# Power.net
KiCad netlist of a schematic drawn in Altium Designer
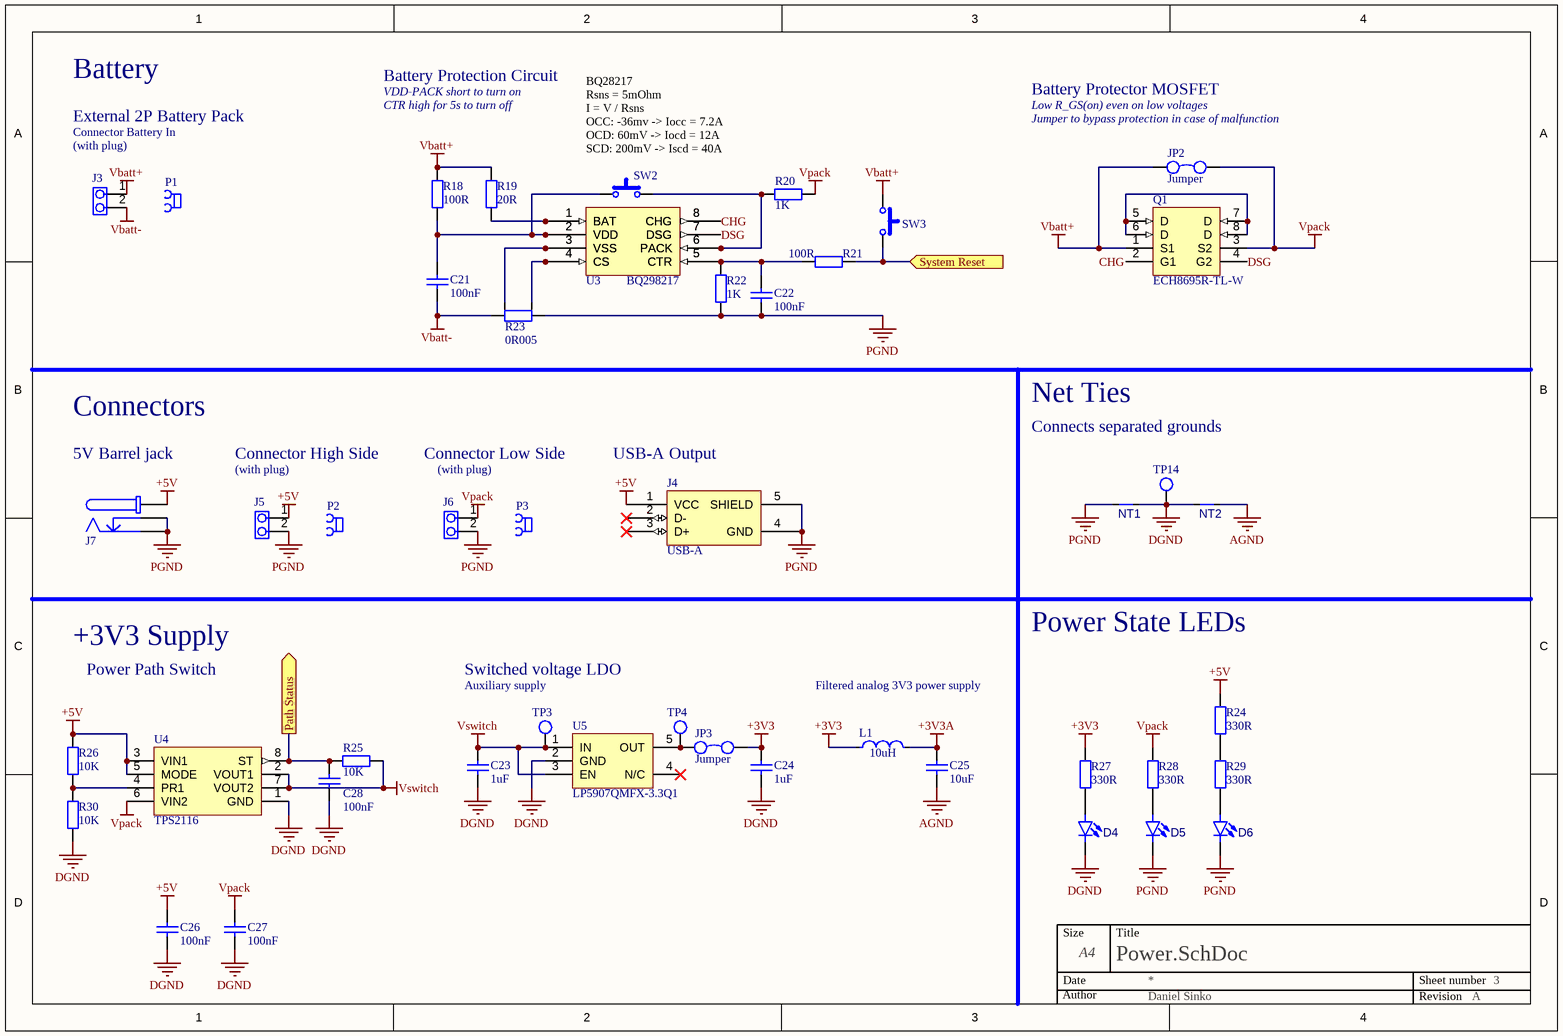
[diagram p0: Power.SchDoc]

(export (version "E")
  (design (tool "Eeschema 10.0.6"))
  (components
    (comp (ref "C21")
      (value "100nF")
      (footprint "CAP0603")
      (fields
        (field (name "MANUFACTURER") "Samsung")
        (field (name "MANUFACTURER PART NUMBER") "CL10B104KA8WPNC")
      )
      (libsource (lib "UPS_Schlib") (part "100nF"))
    )
    (comp (ref "C22")
      (value "100nF")
      (footprint "CAP0603")
      (fields
        (field (name "MANUFACTURER") "Samsung")
        (field (name "MANUFACTURER PART NUMBER") "CL10B104KA8WPNC")
      )
      (libsource (lib "UPS_Schlib") (part "100nF"))
    )
    (comp (ref "C23")
      (value "1uF")
      (footprint "CAP0603")
      (fields
        (field (name "MANUFACTURER") "Walsin Technologies")
        (field (name "MANUFACTURER PART NUMBER") "SH18B105K160CT")
      )
      (libsource (lib "UPS_Schlib") (part "1uF"))
    )
    (comp (ref "C24")
      (value "1uF")
      (footprint "CAP0603")
      (fields
        (field (name "MANUFACTURER") "Walsin Technologies")
        (field (name "MANUFACTURER PART NUMBER") "SH18B105K160CT")
      )
      (libsource (lib "UPS_Schlib") (part "1uF"))
    )
    (comp (ref "C25")
      (value "10uF")
      (footprint "CAP0603")
      (fields
        (field (name "MANUFACTURER") "Samsung")
        (field (name "MANUFACTURER PART NUMBER") "CL10A106MQ8NNND")
      )
      (libsource (lib "UPS_Schlib") (part "10uF"))
    )
    (comp (ref "C26")
      (value "100nF")
      (footprint "CAP0603")
      (fields
        (field (name "MANUFACTURER") "Samsung")
        (field (name "MANUFACTURER PART NUMBER") "CL10B104KA8WPNC")
      )
      (libsource (lib "UPS_Schlib") (part "100nF"))
    )
    (comp (ref "C27")
      (value "100nF")
      (footprint "CAP0603")
      (fields
        (field (name "MANUFACTURER") "Samsung")
        (field (name "MANUFACTURER PART NUMBER") "CL10B104KA8WPNC")
      )
      (libsource (lib "UPS_Schlib") (part "100nF"))
    )
    (comp (ref "C28")
      (value "100nF")
      (footprint "CAP0603")
      (fields
        (field (name "MANUFACTURER") "Samsung")
        (field (name "MANUFACTURER PART NUMBER") "CL10B104KA8WPNC")
      )
      (libsource (lib "UPS_Schlib") (part "100nF"))
    )
    (comp (ref "D4")
      (value "~")
      (footprint "LED0603")
      (description "Single Color LED, Bright Green, Water Clear, 1.1mm")
      (fields
        (field (name "MANUFACTURER") "Wurth Electronics")
        (field (name "MANUFACTURER PART NUMBER") "150060VS75000")
      )
      (libsource (lib "UPS_Schlib") (part "LED Green"))
    )
    (comp (ref "D5")
      (value "~")
      (footprint "LED0603")
      (description "Single Color LED, Bright Green, Water Clear, 1.1mm")
      (fields
        (field (name "MANUFACTURER") "Wurth Electronics")
        (field (name "MANUFACTURER PART NUMBER") "150060VS75000")
      )
      (libsource (lib "UPS_Schlib") (part "LED Green"))
    )
    (comp (ref "D6")
      (value "~")
      (footprint "LED0603")
      (description "Single Color LED, Bright Green, Water Clear, 1.1mm")
      (fields
        (field (name "MANUFACTURER") "Wurth Electronics")
        (field (name "MANUFACTURER PART NUMBER") "150060VS75000")
      )
      (libsource (lib "UPS_Schlib") (part "LED Green"))
    )
    (comp (ref "J3")
      (value "691313510002")
      (footprint "WR-TBL-5.08/2-M")
      (description "Wurth Elektronik, 2 Pin Pluggable Terminal Block, Male")
      (fields
        (field (name "MOUSER PART NUMBER") "710-691313510002")
        (field (name "MANUFACTURER") "Wurth Electronics")
        (field (name "SAFETY APPROVAL") "UL,VDE")
      )
      (libsource (lib "UPS_Schlib") (part "691313510002"))
    )
    (comp (ref "J4")
      (value "USB-A")
      (footprint "USB-A-FEMALE")
      (description "USB Connector")
      (fields (field (name "MANUFACTURER") "Bel") (field (name "MANUFACTURER PART NUMBER") "SS-52100-001"))
      (libsource (lib "UPS_Schlib") (part "USB-A"))
    )
    (comp (ref "J5")
      (value "691313510002")
      (footprint "WR-TBL-5.08/2-M")
      (description "Wurth Elektronik, 2 Pin Pluggable Terminal Block, Male")
      (fields
        (field (name "MOUSER PART NUMBER") "710-691313510002")
        (field (name "MANUFACTURER") "Wurth Electronics")
        (field (name "SAFETY APPROVAL") "UL,VDE")
      )
      (libsource (lib "UPS_Schlib") (part "691313510002"))
    )
    (comp (ref "J6")
      (value "691313510002")
      (footprint "WR-TBL-5.08/2-M")
      (description "Wurth Elektronik, 2 Pin Pluggable Terminal Block, Male")
      (fields
        (field (name "MOUSER PART NUMBER") "710-691313510002")
        (field (name "MANUFACTURER") "Wurth Electronics")
        (field (name "SAFETY APPROVAL") "UL,VDE")
      )
      (libsource (lib "UPS_Schlib") (part "691313510002"))
    )
    (comp (ref "J7")
      (value "DC Power Jack")
      (footprint "DC Power Jack Right Angled")
      (description "CIRCULAR DC POWER CONNECTOR")
      (fields
        (field (name "MANUFACTURER") "Wurth Electronics")
        (field (name "MANUFACTURER PART NUMBER") "694106301002")
      )
      (libsource (lib "UPS_Schlib") (part "DC Power Jack"))
    )
    (comp (ref "JP2")
      (value "Jumper")
      (footprint "PIN-1X2")
      (description "Interconnection Device")
      (fields (field (name "MANUFACTURER") "Harwin") (field (name "MANUFACTURER PART NUMBER") "M7582-46"))
      (libsource (lib "UPS_Schlib") (part "Jumper"))
    )
    (comp (ref "JP3")
      (value "Jumper")
      (footprint "PIN-1X2")
      (description "Interconnection Device")
      (fields (field (name "MANUFACTURER") "Harwin") (field (name "MANUFACTURER PART NUMBER") "M7582-46"))
      (libsource (lib "UPS_Schlib") (part "Jumper"))
    )
    (comp (ref "L1")
      (value "10uH")
      (footprint "IND0603")
      (description "General Purpose Inductor, 10uH, 20%, 1 Element, Ferrite-Core, SMD, 1608M")
      (fields (field (name "MANUFACTURER") "TDK") (field (name "MANUFACTURER PART NUMBER") "MLZ1608E100MT"))
      (libsource (lib "UPS_Schlib") (part "10uH"))
    )
    (comp (ref "NT1")
      (value "NetTie_1-1")
      (footprint "NETTIE_1.85MM")
      (description "NetTie 1 -> 1")
      (libsource (lib "UPS_Schlib") (part "NetTie_1-1"))
    )
    (comp (ref "NT2")
      (value "NetTie_1-1")
      (footprint "NETTIE_1.85MM")
      (description "NetTie 1 -> 1")
      (libsource (lib "UPS_Schlib") (part "NetTie_1-1"))
    )
    (comp (ref "P1")
      (value "691351500002")
      (footprint "WR-TBL-5.08/2-F")
      (description "Wurth Elektronik, 2 Pin Pluggable Terminal Block, Female")
      (fields (field (name "MANUFACTURER") "Wurth Electronics"))
      (libsource (lib "UPS_Schlib") (part "691351500002"))
    )
    (comp (ref "P2")
      (value "691351500002")
      (footprint "WR-TBL-5.08/2-F")
      (description "Wurth Elektronik, 2 Pin Pluggable Terminal Block, Female")
      (fields (field (name "MANUFACTURER") "Wurth Electronics"))
      (libsource (lib "UPS_Schlib") (part "691351500002"))
    )
    (comp (ref "P3")
      (value "691351500002")
      (footprint "WR-TBL-5.08/2-F")
      (description "Wurth Elektronik, 2 Pin Pluggable Terminal Block, Female")
      (fields (field (name "MANUFACTURER") "Wurth Electronics"))
      (libsource (lib "UPS_Schlib") (part "691351500002"))
    )
    (comp (ref "Q1")
      (value "ECH8695R-TL-W")
      (footprint "SOT-28FL")
      (description "Power Field-Effect Transistor, 11A I(D), N-Channel, Metal-oxide Semiconductor FET")
      (fields
        (field (name "MOUSER PART NUMBER") "863-ECH8695R-TL-W")
        (field (name "MANUFACTURER") "ON Semiconductor")
      )
      (libsource (lib "UPS_Schlib") (part "ECH8695R-TL-W"))
    )
    (comp (ref "R18")
      (value "100R")
      (footprint "RES0603")
      (fields
        (field (name "MANUFACTURER") "Yageo")
        (field (name "MANUFACTURER PART NUMBER") "RC0603JR-13100RL")
      )
      (libsource (lib "") (part "100R_1"))
    )
    (comp (ref "R19")
      (value "20R")
      (footprint "RES0603")
      (fields
        (field (name "MANUFACTURER") "Vishay")
        (field (name "MANUFACTURER PART NUMBER") "CRCW060320R0FKEA")
      )
      (libsource (lib "UPS_Schlib") (part "20R"))
    )
    (comp (ref "R20")
      (value "1K")
      (footprint "RES0603")
      (fields
        (field (name "MANUFACTURER") "Bourns")
        (field (name "MANUFACTURER PART NUMBER") "CR0603-FX-1001ELF")
      )
      (libsource (lib "") (part "1K_1"))
    )
    (comp (ref "R21")
      (value "100R")
      (footprint "RES0603")
      (fields
        (field (name "MANUFACTURER") "Yageo")
        (field (name "MANUFACTURER PART NUMBER") "RC0603JR-13100RL")
      )
      (libsource (lib "UPS_Schlib") (part "100R"))
    )
    (comp (ref "R22")
      (value "1K")
      (footprint "RES0603")
      (fields
        (field (name "MANUFACTURER") "Bourns")
        (field (name "MANUFACTURER PART NUMBER") "CR0603-FX-1001ELF")
      )
      (libsource (lib "UPS_Schlib") (part "1K"))
    )
    (comp (ref "R23")
      (value "0R005")
      (footprint "RES1206_KELVIN")
      (description "Resistor Current Sense Metal Foil 1206 5m Ohm 1% 1W ±50ppm/°C T/R")
      (fields
        (field (name "MANUFACTURER") "Eaton")
        (field (name "MANUFACTURER PART NUMBER") "MFSA1206R0050FCM")
      )
      (libsource (lib "UPS_Schlib") (part "0R005"))
    )
    (comp (ref "R24")
      (value "330R")
      (footprint "RES0603")
      (fields
        (field (name "MANUFACTURER") "Walsin Technologies")
        (field (name "MANUFACTURER PART NUMBER") "WR06X3300FTL")
      )
      (libsource (lib "UPS_Schlib") (part "330R"))
    )
    (comp (ref "R25")
      (value "10K")
      (footprint "RES0603")
      (fields
        (field (name "MANUFACTURER") "Bourns")
        (field (name "MANUFACTURER PART NUMBER") "CR0603-FX-1002ELF")
      )
      (libsource (lib "UPS_Schlib") (part "10K"))
    )
    (comp (ref "R26")
      (value "10K")
      (footprint "RES0603")
      (fields
        (field (name "MANUFACTURER") "Bourns")
        (field (name "MANUFACTURER PART NUMBER") "CR0603-FX-1002ELF")
      )
      (libsource (lib "") (part "10K_1"))
    )
    (comp (ref "R27")
      (value "330R")
      (footprint "RES0603")
      (fields
        (field (name "MANUFACTURER") "Walsin Technologies")
        (field (name "MANUFACTURER PART NUMBER") "WR06X3300FTL")
      )
      (libsource (lib "UPS_Schlib") (part "330R"))
    )
    (comp (ref "R28")
      (value "330R")
      (footprint "RES0603")
      (fields
        (field (name "MANUFACTURER") "Walsin Technologies")
        (field (name "MANUFACTURER PART NUMBER") "WR06X3300FTL")
      )
      (libsource (lib "UPS_Schlib") (part "330R"))
    )
    (comp (ref "R29")
      (value "330R")
      (footprint "RES0603")
      (fields
        (field (name "MANUFACTURER") "Walsin Technologies")
        (field (name "MANUFACTURER PART NUMBER") "WR06X3300FTL")
      )
      (libsource (lib "UPS_Schlib") (part "330R"))
    )
    (comp (ref "R30")
      (value "10K")
      (footprint "RES0603")
      (fields
        (field (name "MANUFACTURER") "Bourns")
        (field (name "MANUFACTURER PART NUMBER") "CR0603-FX-1002ELF")
      )
      (libsource (lib "") (part "10K_1"))
    )
    (comp (ref "SW2")
      (value "PTS526 Button")
      (footprint "PTS526 SMG15J SMTR2 LFS")
      (description "PTS526 Series SPST-NO Off-Mom 160 gf Top Actuated J Lead SMT Tactile Switch")
      (fields
        (field (name "MANUFACTURER") "ITT C&K")
        (field (name "MANUFACTURER PART NUMBER") "PTS526SMG15JSMTR2LFS")
      )
      (libsource (lib "UPS_Schlib") (part "PTS526 Button"))
    )
    (comp (ref "SW3")
      (value "PTS526 Button")
      (footprint "PTS526 SMG15J SMTR2 LFS")
      (description "PTS526 Series SPST-NO Off-Mom 160 gf Top Actuated J Lead SMT Tactile Switch")
      (fields
        (field (name "MANUFACTURER") "ITT C&K")
        (field (name "MANUFACTURER PART NUMBER") "PTS526SMG15JSMTR2LFS")
      )
      (libsource (lib "UPS_Schlib") (part "PTS526 Button"))
    )
    (comp (ref "TP3")
      (value "Test Point")
      (footprint "TP-1.5HOLE")
      (libsource (lib "UPS_Schlib") (part "Test Point"))
    )
    (comp (ref "TP4")
      (value "Test Point")
      (footprint "TP-1.5HOLE")
      (libsource (lib "UPS_Schlib") (part "Test Point"))
    )
    (comp (ref "TP14")
      (value "Test Point")
      (footprint "TP-1.5HOLE")
      (libsource (lib "UPS_Schlib") (part "Test Point"))
    )
    (comp (ref "U3")
      (value "BQ298217")
      (footprint "X2QFN-8")
      (fields
        (field (name "MANUFACTURER") "Texas Instruments")
        (field (name "MANUFACTURER PART NUMBER") "BQ298217RUGR")
      )
      (libsource (lib "UPS_Schlib") (part "BQ2980"))
    )
    (comp (ref "U4")
      (value "TPS2116")
      (footprint "SOTFL50P160X60-8N")
      (description "Single-Ended Multiplexer, 1 Func, 2 Channel, PDSO8")
      (fields
        (field (name "MANUFACTURER") "Texas Instruments")
        (field (name "MANUFACTURER PART NUMBER") "TPS2116DRLR")
      )
      (libsource (lib "UPS_Schlib") (part "TPS2116"))
    )
    (comp (ref "U5")
      (value "LP5907QMFX-3.3Q1")
      (footprint "SOT23-5")
      (description "Fixed Positive LDO Regulator, 3.3V, 0.25V Dropout, PDSO5")
      (fields
        (field (name "MOUSER PART NUMBER") "595-LP5907QMFX-3.3Q1")
        (field (name "MANUFACTURER") "Texas Instruments")
      )
      (libsource (lib "UPS_Schlib") (part "LP5907QMFX-3.3Q1"))
    )
  )
  (nets
    (net (code "1") (name "+3V3") (class "Default")
      (node (ref "C24") (pin "2") (pinfunction "2_2") (pintype "passive"))
      (node (ref "JP3") (pin "2") (pintype "passive"))
      (node (ref "L1") (pin "1") (pinfunction "1_1") (pintype "passive"))
      (node (ref "R27") (pin "2") (pinfunction "2_2") (pintype "passive"))
    )
    (net (code "2") (name "+3V3A") (class "Default")
      (node (ref "C25") (pin "2") (pinfunction "2_2") (pintype "passive"))
      (node (ref "L1") (pin "2") (pinfunction "2_2") (pintype "passive"))
    )
    (net (code "3") (name "+5V") (class "Default")
      (node (ref "C26") (pin "2") (pinfunction "2_2") (pintype "passive"))
      (node (ref "J4") (pin "1") (pinfunction "VCC_1") (pintype "power_in"))
      (node (ref "J5") (pin "1") (pinfunction "1_1") (pintype "passive"))
      (node (ref "J7") (pin "1") (pinfunction "1_1") (pintype "passive"))
      (node (ref "R24") (pin "2") (pinfunction "2_2") (pintype "passive"))
      (node (ref "R26") (pin "2") (pinfunction "2_2") (pintype "passive"))
      (node (ref "U4") (pin "3") (pinfunction "VIN1_3") (pintype "passive"))
      (node (ref "U4") (pin "5") (pinfunction "MODE_5") (pintype "passive"))
    )
    (net (code "4") (name "/CHG") (class "Default")
      (node (ref "Q1") (pin "2") (pinfunction "G1_2") (pintype "passive"))
      (node (ref "U3") (pin "8") (pinfunction "CHG_8") (pintype "output"))
    )
    (net (code "5") (name "/DSG") (class "Default")
      (node (ref "Q1") (pin "4") (pinfunction "G2_4") (pintype "passive"))
      (node (ref "U3") (pin "7") (pinfunction "DSG_7") (pintype "output"))
    )
    (net (code "6") (name "/Path Status") (class "Default")
      (node (ref "C28") (pin "2") (pinfunction "2_2") (pintype "passive"))
      (node (ref "R25") (pin "2") (pinfunction "2_2") (pintype "passive"))
      (node (ref "U4") (pin "8") (pinfunction "ST_8") (pintype "output"))
    )
    (net (code "7") (name "/System Reset") (class "Default")
      (node (ref "R21") (pin "2") (pinfunction "2_2") (pintype "passive"))
      (node (ref "SW3") (pin "2") (pinfunction "2_2") (pintype "passive"))
    )
    (net (code "8") (name "AGND") (class "Default")
      (node (ref "C25") (pin "1") (pinfunction "1_1") (pintype "passive"))
      (node (ref "NT2") (pin "2") (pinfunction "2_2") (pintype "passive"))
    )
    (net (code "9") (name "DGND") (class "Default")
      (node (ref "C23") (pin "1") (pinfunction "1_1") (pintype "passive"))
      (node (ref "C24") (pin "1") (pinfunction "1_1") (pintype "passive"))
      (node (ref "C26") (pin "1") (pinfunction "1_1") (pintype "passive"))
      (node (ref "C27") (pin "1") (pinfunction "1_1") (pintype "passive"))
      (node (ref "C28") (pin "1") (pinfunction "1_1") (pintype "passive"))
      (node (ref "D4") (pin "1") (pinfunction "K_1") (pintype "passive"))
      (node (ref "NT1") (pin "2") (pinfunction "2_2") (pintype "passive"))
      (node (ref "NT2") (pin "1") (pinfunction "1_1") (pintype "passive"))
      (node (ref "R30") (pin "1") (pinfunction "1_1") (pintype "passive"))
      (node (ref "TP14") (pin "1") (pintype "passive"))
      (node (ref "U4") (pin "1") (pinfunction "GND_1") (pintype "passive"))
      (node (ref "U5") (pin "2") (pinfunction "GND_2") (pintype "passive"))
    )
    (net (code "10") (name "Net-(D4-A)") (class "Default")
      (node (ref "D4") (pin "2") (pinfunction "A_2") (pintype "passive"))
      (node (ref "R27") (pin "1") (pinfunction "1_1") (pintype "passive"))
    )
    (net (code "11") (name "Net-(D5-A)") (class "Default")
      (node (ref "D5") (pin "2") (pinfunction "A_2") (pintype "passive"))
      (node (ref "R28") (pin "1") (pinfunction "1_1") (pintype "passive"))
    )
    (net (code "12") (name "Net-(D6-A)") (class "Default")
      (node (ref "D6") (pin "2") (pinfunction "A_2") (pintype "passive"))
      (node (ref "R29") (pin "1") (pinfunction "1_1") (pintype "passive"))
    )
    (net (code "13") (name "Net-(Q1-D-Pad5)") (class "Default")
      (node (ref "Q1") (pin "5") (pinfunction "D_5") (pintype "input"))
      (node (ref "Q1") (pin "6") (pinfunction "D_6") (pintype "input"))
      (node (ref "Q1") (pin "7") (pinfunction "D_7") (pintype "input"))
      (node (ref "Q1") (pin "8") (pinfunction "D_8") (pintype "input"))
    )
    (net (code "14") (name "Net-(R24-Pad1)") (class "Default")
      (node (ref "R24") (pin "1") (pinfunction "1_1") (pintype "passive"))
      (node (ref "R29") (pin "2") (pinfunction "2_2") (pintype "passive"))
    )
    (net (code "15") (name "Net-(U3-BAT)") (class "Default")
      (node (ref "R19") (pin "1") (pinfunction "1_1") (pintype "passive"))
      (node (ref "U3") (pin "1") (pinfunction "BAT_1") (pintype "input"))
    )
    (net (code "16") (name "Net-(U3-CS)") (class "Default")
      (node (ref "R23") (pin "4") (pinfunction "4_4") (pintype "passive"))
      (node (ref "U3") (pin "4") (pinfunction "CS_4") (pintype "input"))
    )
    (net (code "17") (name "Net-(U3-CTR)") (class "Default")
      (node (ref "C22") (pin "2") (pinfunction "2_2") (pintype "passive"))
      (node (ref "R21") (pin "1") (pinfunction "1_1") (pintype "passive"))
      (node (ref "R22") (pin "2") (pinfunction "2_2") (pintype "passive"))
      (node (ref "U3") (pin "5") (pinfunction "CTR_5") (pintype "input"))
    )
    (net (code "18") (name "Net-(U3-PACK)") (class "Default")
      (node (ref "R20") (pin "1") (pinfunction "1_1") (pintype "passive"))
      (node (ref "SW2") (pin "2") (pinfunction "2_2") (pintype "passive"))
      (node (ref "U3") (pin "6") (pinfunction "PACK_6") (pintype "input"))
    )
    (net (code "19") (name "Net-(U3-VDD)") (class "Default")
      (node (ref "C21") (pin "2") (pinfunction "2_2") (pintype "passive"))
      (node (ref "R18") (pin "1") (pinfunction "1_1") (pintype "passive"))
      (node (ref "SW2") (pin "1") (pinfunction "1_1") (pintype "passive"))
      (node (ref "U3") (pin "2") (pinfunction "VDD_2") (pintype "power_in"))
    )
    (net (code "20") (name "Net-(U3-VSS)") (class "Default")
      (node (ref "R23") (pin "3") (pinfunction "3_3") (pintype "passive"))
      (node (ref "U3") (pin "3") (pinfunction "VSS_3") (pintype "passive"))
    )
    (net (code "21") (name "Net-(U4-PR1)") (class "Default")
      (node (ref "R26") (pin "1") (pinfunction "1_1") (pintype "passive"))
      (node (ref "R30") (pin "2") (pinfunction "2_2") (pintype "passive"))
      (node (ref "U4") (pin "4") (pinfunction "PR1_4") (pintype "passive"))
    )
    (net (code "22") (name "Net-(U5-OUT)") (class "Default")
      (node (ref "JP3") (pin "1") (pintype "passive"))
      (node (ref "TP4") (pin "1") (pintype "passive"))
      (node (ref "U5") (pin "5") (pinfunction "OUT_5") (pintype "passive"))
    )
    (net (code "23") (name "PGND") (class "Default")
      (node (ref "C22") (pin "1") (pinfunction "1_1") (pintype "passive"))
      (node (ref "D5") (pin "1") (pinfunction "K_1") (pintype "passive"))
      (node (ref "D6") (pin "1") (pinfunction "K_1") (pintype "passive"))
      (node (ref "J4") (pin "4") (pinfunction "GND_4") (pintype "passive"))
      (node (ref "J4") (pin "5") (pinfunction "SHIELD_5") (pintype "passive"))
      (node (ref "J5") (pin "2") (pinfunction "2_2") (pintype "passive"))
      (node (ref "J6") (pin "2") (pinfunction "2_2") (pintype "passive"))
      (node (ref "J7") (pin "2") (pinfunction "2_2") (pintype "passive"))
      (node (ref "J7") (pin "3") (pinfunction "3_3") (pintype "passive"))
      (node (ref "NT1") (pin "1") (pinfunction "1_1") (pintype "passive"))
      (node (ref "R22") (pin "1") (pinfunction "1_1") (pintype "passive"))
      (node (ref "R23") (pin "2") (pinfunction "2_2") (pintype "passive"))
    )
    (net (code "24") (name "Vbatt+") (class "Default")
      (node (ref "J3") (pin "1") (pinfunction "1_1") (pintype "passive"))
      (node (ref "JP2") (pin "1") (pintype "passive"))
      (node (ref "Q1") (pin "1") (pinfunction "S1_1") (pintype "passive"))
      (node (ref "R18") (pin "2") (pinfunction "2_2") (pintype "passive"))
      (node (ref "R19") (pin "2") (pinfunction "2_2") (pintype "passive"))
      (node (ref "SW3") (pin "1") (pinfunction "1_1") (pintype "passive"))
    )
    (net (code "25") (name "Vbatt-") (class "Default")
      (node (ref "C21") (pin "1") (pinfunction "1_1") (pintype "passive"))
      (node (ref "J3") (pin "2") (pinfunction "2_2") (pintype "passive"))
      (node (ref "R23") (pin "1") (pinfunction "1_1") (pintype "passive"))
    )
    (net (code "26") (name "Vpack") (class "Default")
      (node (ref "C27") (pin "2") (pinfunction "2_2") (pintype "passive"))
      (node (ref "J6") (pin "1") (pinfunction "1_1") (pintype "passive"))
      (node (ref "JP2") (pin "2") (pintype "passive"))
      (node (ref "Q1") (pin "3") (pinfunction "S2_3") (pintype "passive"))
      (node (ref "R20") (pin "2") (pinfunction "2_2") (pintype "passive"))
      (node (ref "R28") (pin "2") (pinfunction "2_2") (pintype "passive"))
      (node (ref "U4") (pin "6") (pinfunction "VIN2_6") (pintype "passive"))
    )
    (net (code "27") (name "Vswitch") (class "Default")
      (node (ref "C23") (pin "2") (pinfunction "2_2") (pintype "passive"))
      (node (ref "R25") (pin "1") (pinfunction "1_1") (pintype "passive"))
      (node (ref "TP3") (pin "1") (pintype "passive"))
      (node (ref "U4") (pin "2") (pinfunction "VOUT1_2") (pintype "passive"))
      (node (ref "U4") (pin "7") (pinfunction "VOUT2_7") (pintype "passive"))
      (node (ref "U5") (pin "1") (pinfunction "IN_1") (pintype "passive"))
      (node (ref "U5") (pin "3") (pinfunction "EN_3") (pintype "passive"))
    )
    (net (code "28") (name "unconnected-(J4-D+-Pad3)") (class "Default")
      (node (ref "J4") (pin "3") (pinfunction "D+_3") (pintype "bidirectional+no_connect"))
    )
    (net (code "29") (name "unconnected-(J4-D--Pad2)") (class "Default")
      (node (ref "J4") (pin "2") (pinfunction "D-_2") (pintype "bidirectional+no_connect"))
    )
    (net (code "30") (name "unconnected-(U5-N{slash}C-Pad4)") (class "Default")
      (node (ref "U5") (pin "4") (pinfunction "N/C_4") (pintype "passive+no_connect"))
    )
  )
)
